# PSU_R1.net
KiCad netlist of a schematic drawn in EAGLE
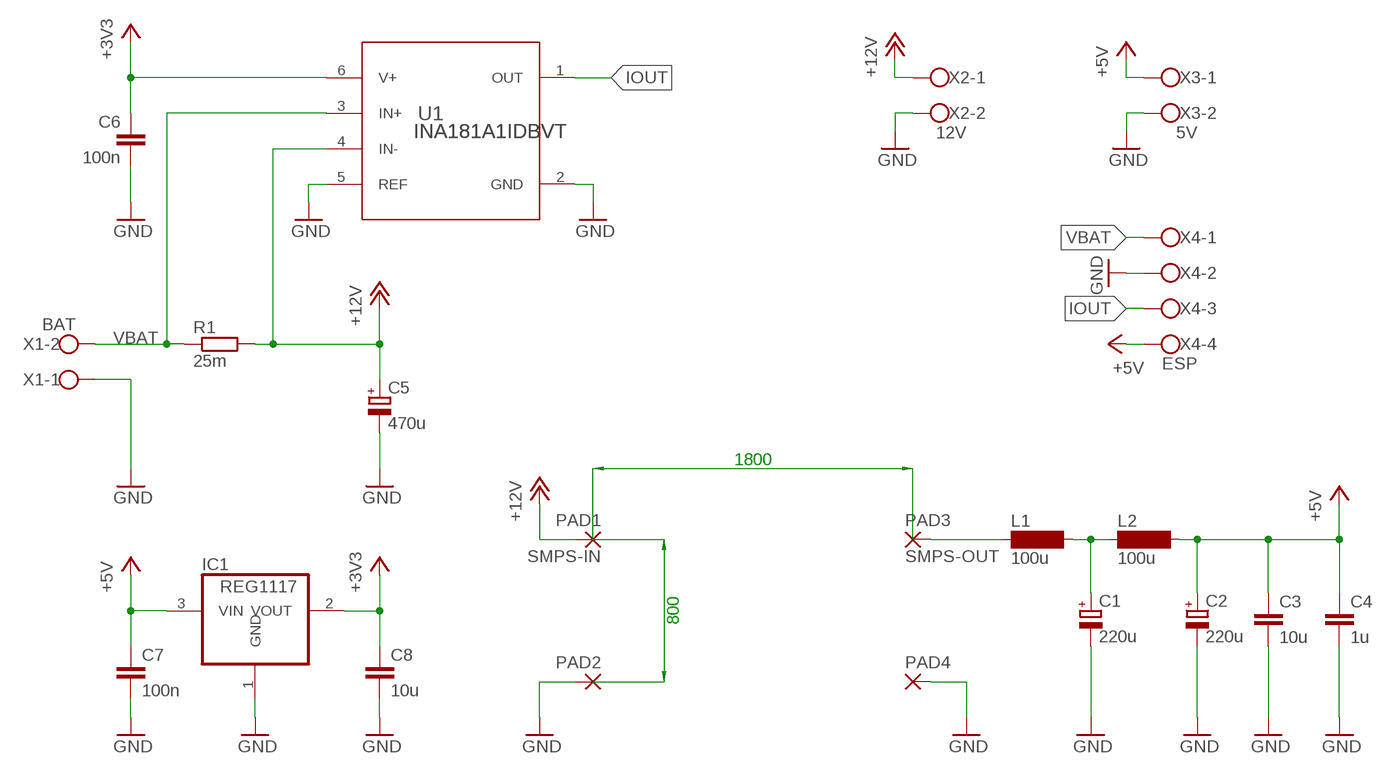
[diagram p0: schematic, sheet 1]

(export (version "E")
  (design (tool "Eeschema 10.0.6"))
  (components
    (comp (ref "C1")
      (value "220u")
      (footprint "eagle-import:E2,5-6")
      (libsource (lib "eagle-import") (part "CPOL-EUE2.5-6"))
    )
    (comp (ref "C2")
      (value "220u")
      (footprint "eagle-import:E2,5-6")
      (libsource (lib "eagle-import") (part "CPOL-EUE2.5-6"))
    )
    (comp (ref "C3")
      (value "10u")
      (footprint "eagle-import:C1206")
      (libsource (lib "eagle-import") (part "C-EUC1206"))
    )
    (comp (ref "C4")
      (value "1u")
      (footprint "eagle-import:C0805")
      (libsource (lib "eagle-import") (part "C-EUC0805"))
    )
    (comp (ref "C5")
      (value "470u")
      (footprint "eagle-import:E5-10,5")
      (libsource (lib "eagle-import") (part "CPOL-EUE5-10.5"))
    )
    (comp (ref "C6")
      (value "100n")
      (footprint "eagle-import:C0603")
      (libsource (lib "eagle-import") (part "C-EUC0603"))
    )
    (comp (ref "C7")
      (value "100n")
      (footprint "eagle-import:C0603")
      (libsource (lib "eagle-import") (part "C-EUC0603"))
    )
    (comp (ref "C8")
      (value "10u")
      (footprint "eagle-import:C1206")
      (libsource (lib "eagle-import") (part "C-EUC1206"))
    )
    (comp (ref "IC1")
      (value "REG1117")
      (footprint "eagle-import:SOT223")
      (libsource (lib "eagle-import") (part "REG1117"))
    )
    (comp (ref "L1")
      (value "100u")
      (footprint "eagle-import:SD8")
      (libsource (lib "eagle-import") (part "SD8"))
    )
    (comp (ref "L2")
      (value "100u")
      (footprint "eagle-import:SD8")
      (libsource (lib "eagle-import") (part "SD8"))
    )
    (comp (ref "PAD1")
      (value "SMPS-IN")
      (footprint "eagle-import:1,6_0,9")
      (libsource (lib "eagle-import") (part "1,6/0,9"))
    )
    (comp (ref "PAD2")
      (value "1,6/0,9")
      (footprint "eagle-import:1,6_0,9")
      (libsource (lib "eagle-import") (part "1,6/0,9"))
    )
    (comp (ref "PAD3")
      (value "SMPS-OUT")
      (footprint "eagle-import:1,6_0,9")
      (libsource (lib "eagle-import") (part "1,6/0,9"))
    )
    (comp (ref "PAD4")
      (value "1,6/0,9")
      (footprint "eagle-import:1,6_0,9")
      (libsource (lib "eagle-import") (part "1,6/0,9"))
    )
    (comp (ref "R1")
      (value "25m")
      (footprint "eagle-import:R2512")
      (libsource (lib "eagle-import") (part "R-EU_R2512"))
    )
    (comp (ref "U1")
      (value "INA181A1IDBVT")
      (footprint "eagle-import:DBV0006A_N")
      (fields (field (name "COPYRIGHT") "Copyright (C) 2023 Ultra Librarian. All rights reserved."))
      (libsource (lib "eagle-import") (part "INA181A1IDBVT"))
    )
    (comp (ref "X1")
      (value "BAT")
      (footprint "eagle-import:W237-102")
      (fields (field (name "MPN") "237-102"))
      (libsource (lib "eagle-import") (part "W237-102"))
    )
    (comp (ref "X2")
      (value "12V")
      (footprint "eagle-import:W237-102")
      (fields (field (name "MPN") "237-102"))
      (libsource (lib "eagle-import") (part "W237-102"))
    )
    (comp (ref "X3")
      (value "5V")
      (footprint "eagle-import:W237-102")
      (fields (field (name "MPN") "237-102"))
      (libsource (lib "eagle-import") (part "W237-102"))
    )
    (comp (ref "X4")
      (value "ESP")
      (footprint "eagle-import:W237-4")
      (libsource (lib "eagle-import") (part "W237-4"))
    )
  )
  (nets
    (net (code "1") (name "+3V3") (class "Default")
      (node (ref "C6") (pin "1") (pinfunction "1_1") (pintype "passive"))
      (node (ref "C8") (pin "1") (pinfunction "1_1") (pintype "passive"))
      (node (ref "IC1") (pin "2") (pinfunction "VOUT_2") (pintype "output"))
      (node (ref "U1") (pin "6") (pinfunction "V+_6") (pintype "power_in"))
    )
    (net (code "2") (name "+5V") (class "Default")
      (node (ref "C2") (pin "+") (pinfunction "+_+") (pintype "passive"))
      (node (ref "C3") (pin "1") (pinfunction "1_1") (pintype "passive"))
      (node (ref "C4") (pin "1") (pinfunction "1_1") (pintype "passive"))
      (node (ref "C7") (pin "1") (pinfunction "1_1") (pintype "passive"))
      (node (ref "IC1") (pin "3") (pinfunction "VIN_3") (pintype "input"))
      (node (ref "L2") (pin "2") (pinfunction "2_2") (pintype "passive"))
      (node (ref "X3") (pin "1") (pinfunction "KL_1") (pintype "passive"))
      (node (ref "X4") (pin "4") (pinfunction "KL_4") (pintype "passive"))
    )
    (net (code "3") (name "+12V") (class "Default")
      (node (ref "C5") (pin "+") (pinfunction "+_+") (pintype "passive"))
      (node (ref "PAD1") (pin "1") (pinfunction "P_1") (pintype "passive"))
      (node (ref "R1") (pin "2") (pinfunction "2_2") (pintype "passive"))
      (node (ref "U1") (pin "4") (pinfunction "IN-_4") (pintype "input"))
      (node (ref "X2") (pin "1") (pinfunction "KL_1") (pintype "passive"))
    )
    (net (code "4") (name "GND") (class "Default")
      (node (ref "C1") (pin "-") (pinfunction "-_-") (pintype "passive"))
      (node (ref "C2") (pin "-") (pinfunction "-_-") (pintype "passive"))
      (node (ref "C3") (pin "2") (pinfunction "2_2") (pintype "passive"))
      (node (ref "C4") (pin "2") (pinfunction "2_2") (pintype "passive"))
      (node (ref "C5") (pin "-") (pinfunction "-_-") (pintype "passive"))
      (node (ref "C6") (pin "2") (pinfunction "2_2") (pintype "passive"))
      (node (ref "C7") (pin "2") (pinfunction "2_2") (pintype "passive"))
      (node (ref "C8") (pin "2") (pinfunction "2_2") (pintype "passive"))
      (node (ref "IC1") (pin "1") (pinfunction "GND_1") (pintype "power_in"))
      (node (ref "PAD2") (pin "1") (pinfunction "P_1") (pintype "passive"))
      (node (ref "PAD4") (pin "1") (pinfunction "P_1") (pintype "passive"))
      (node (ref "U1") (pin "2") (pinfunction "GND_2") (pintype "power_in"))
      (node (ref "U1") (pin "5") (pinfunction "REF_5") (pintype "input"))
      (node (ref "X1") (pin "1") (pinfunction "KL_1") (pintype "passive"))
      (node (ref "X2") (pin "2") (pinfunction "KL_2") (pintype "passive"))
      (node (ref "X3") (pin "2") (pinfunction "KL_2") (pintype "passive"))
      (node (ref "X4") (pin "2") (pinfunction "KL_2") (pintype "passive"))
    )
    (net (code "5") (name "IOUT") (class "Default")
      (node (ref "U1") (pin "1") (pinfunction "OUT_1") (pintype "output"))
      (node (ref "X4") (pin "3") (pinfunction "KL_3") (pintype "passive"))
    )
    (net (code "6") (name "Net-(C1-Pad+)") (class "Default")
      (node (ref "C1") (pin "+") (pinfunction "+_+") (pintype "passive"))
      (node (ref "L1") (pin "2") (pinfunction "2_2") (pintype "passive"))
      (node (ref "L2") (pin "1") (pinfunction "1_1") (pintype "passive"))
    )
    (net (code "7") (name "Net-(PAD3-P)") (class "Default")
      (node (ref "L1") (pin "1") (pinfunction "1_1") (pintype "passive"))
      (node (ref "PAD3") (pin "1") (pinfunction "P_1") (pintype "passive"))
    )
    (net (code "8") (name "VBAT") (class "Default")
      (node (ref "R1") (pin "1") (pinfunction "1_1") (pintype "passive"))
      (node (ref "U1") (pin "3") (pinfunction "IN+_3") (pintype "input"))
      (node (ref "X1") (pin "2") (pinfunction "KL_2") (pintype "passive"))
      (node (ref "X4") (pin "1") (pinfunction "KL_1") (pintype "passive"))
    )
  )
)
